# design.net
KiCad netlist of a schematic drawn in EasyEDA Pro
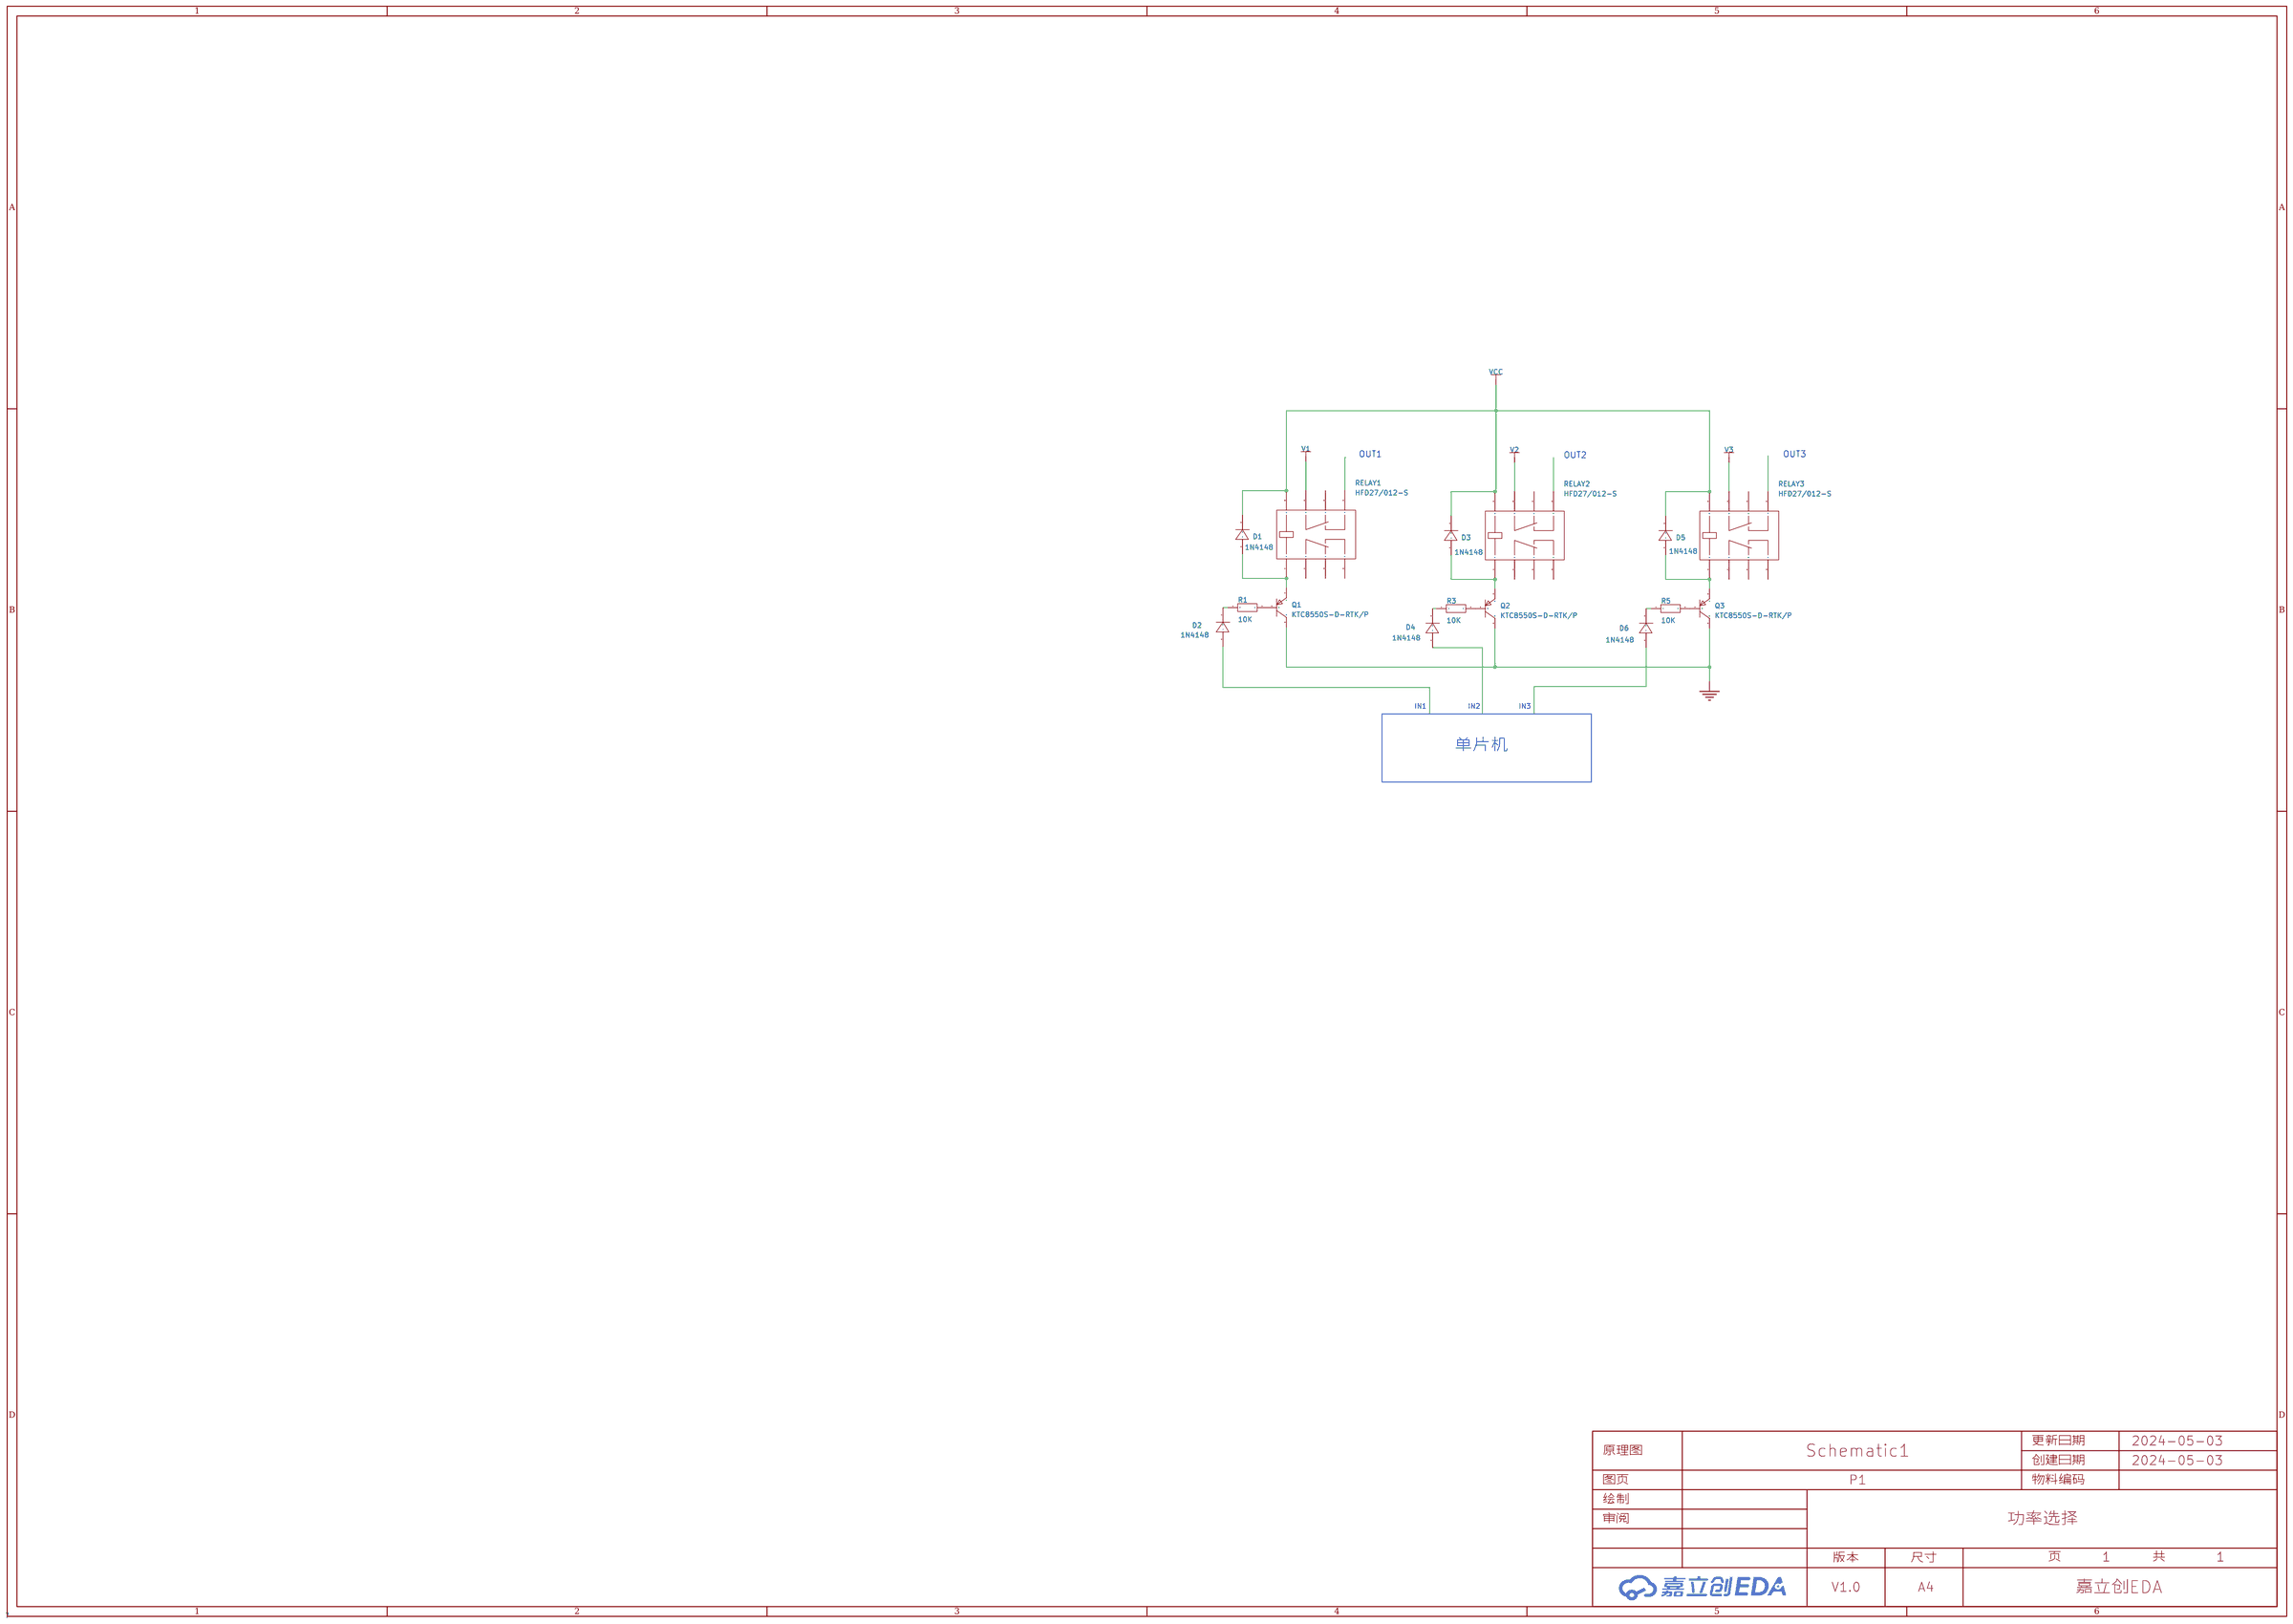
[diagram p0: schematic sheet]

(export (version "E")
  (design (tool "Eeschema 10.0.6"))
  (components
    (comp (ref "D1")
      (value "1N4148")
      (footprint "easyedapro:DO-35_BD2.0-L4.2-P8.20-D0.5-RD")
      (description "二极管配置:-;正向压降(Vf):1V@10mA;直流反向耐压(Vr):75V;平均整流电流(Io):150mA;功率:500mW;反向恢复时间(trr):4ns;")
      (fields (field (name "Manufacturer") "LGE(鲁光)"))
      (libsource (lib "easyedapro") (part "1N4148_C402212"))
    )
    (comp (ref "D2")
      (value "1N4148")
      (footprint "easyedapro:DO-35_BD2.0-L4.2-P8.20-D0.5-RD")
      (description "二极管配置:-;正向压降(Vf):1V@10mA;直流反向耐压(Vr):75V;平均整流电流(Io):150mA;功率:500mW;反向恢复时间(trr):4ns;")
      (fields (field (name "Manufacturer") "LGE(鲁光)"))
      (libsource (lib "easyedapro") (part "1N4148_C402212"))
    )
    (comp (ref "D3")
      (value "1N4148")
      (footprint "easyedapro:DO-35_BD2.0-L4.2-P8.20-D0.5-RD")
      (description "二极管配置:-;正向压降(Vf):1V@10mA;直流反向耐压(Vr):75V;平均整流电流(Io):150mA;功率:500mW;反向恢复时间(trr):4ns;")
      (fields (field (name "Manufacturer") "LGE(鲁光)"))
      (libsource (lib "easyedapro") (part "1N4148_C402212"))
    )
    (comp (ref "D4")
      (value "1N4148")
      (footprint "easyedapro:DO-35_BD2.0-L4.2-P8.20-D0.5-RD")
      (description "二极管配置:-;正向压降(Vf):1V@10mA;直流反向耐压(Vr):75V;平均整流电流(Io):150mA;功率:500mW;反向恢复时间(trr):4ns;")
      (fields (field (name "Manufacturer") "LGE(鲁光)"))
      (libsource (lib "easyedapro") (part "1N4148_C402212"))
    )
    (comp (ref "D5")
      (value "1N4148")
      (footprint "easyedapro:DO-35_BD2.0-L4.2-P8.20-D0.5-RD")
      (description "二极管配置:-;正向压降(Vf):1V@10mA;直流反向耐压(Vr):75V;平均整流电流(Io):150mA;功率:500mW;反向恢复时间(trr):4ns;")
      (fields (field (name "Manufacturer") "LGE(鲁光)"))
      (libsource (lib "easyedapro") (part "1N4148_C402212"))
    )
    (comp (ref "D6")
      (value "1N4148")
      (footprint "easyedapro:DO-35_BD2.0-L4.2-P8.20-D0.5-RD")
      (description "二极管配置:-;正向压降(Vf):1V@10mA;直流反向耐压(Vr):75V;平均整流电流(Io):150mA;功率:500mW;反向恢复时间(trr):4ns;")
      (fields (field (name "Manufacturer") "LGE(鲁光)"))
      (libsource (lib "easyedapro") (part "1N4148_C402212"))
    )
    (comp (ref "Q1")
      (value "KTC8550S-D-RTK/P")
      (footprint "easyedapro:SOT-23-3_L2.9-W1.3-P1.90-LS2.4-TR-CW")
      (description "晶体管类型:PNP;集电极电流(Ic):800mA;集射极击穿电压(Vceo):30V;功率(Pd):350mW;直流电流增益(hFE@Ic,Vce):100@50mA,1V;")
      (fields (field (name "Manufacturer") "KEC"))
      (libsource (lib "easyedapro") (part "KTC8550S-D-RTK/P"))
    )
    (comp (ref "Q2")
      (value "KTC8550S-D-RTK/P")
      (footprint "easyedapro:SOT-23-3_L2.9-W1.3-P1.90-LS2.4-TR-CW")
      (description "晶体管类型:PNP;集电极电流(Ic):800mA;集射极击穿电压(Vceo):30V;功率(Pd):350mW;直流电流增益(hFE@Ic,Vce):100@50mA,1V;")
      (fields (field (name "Manufacturer") "KEC"))
      (libsource (lib "easyedapro") (part "KTC8550S-D-RTK/P"))
    )
    (comp (ref "Q3")
      (value "KTC8550S-D-RTK/P")
      (footprint "easyedapro:SOT-23-3_L2.9-W1.3-P1.90-LS2.4-TR-CW")
      (description "晶体管类型:PNP;集电极电流(Ic):800mA;集射极击穿电压(Vceo):30V;功率(Pd):350mW;直流电流增益(hFE@Ic,Vce):100@50mA,1V;")
      (fields (field (name "Manufacturer") "KEC"))
      (libsource (lib "easyedapro") (part "KTC8550S-D-RTK/P"))
    )
    (comp (ref "R1") (value "10K") (footprint "easyedapro:R0603") (libsource (lib "easyedapro") (part "电阻")))
    (comp (ref "R3") (value "10K") (footprint "easyedapro:R0603") (libsource (lib "easyedapro") (part "电阻")))
    (comp (ref "R5") (value "10K") (footprint "easyedapro:R0603") (libsource (lib "easyedapro") (part "电阻")))
    (comp (ref "RELAY1")
      (value "HFD27/012-S")
      (footprint "easyedapro:RELAY-TH_HFD27-012-S")
      (description "线圈电压:12V;触点形式:两组转换:2C(双刀双掷-转换);触点容量(电阻负载):2A@30VDC；1A@125VAC;最大切换电压:120V@DC；240V@AC;最大切换电流:2A;")
      (fields (field (name "Manufacturer") "HF(宏发)"))
      (libsource (lib "easyedapro") (part "HFD27/012-S"))
    )
    (comp (ref "RELAY2")
      (value "HFD27/012-S")
      (footprint "easyedapro:RELAY-TH_HFD27-012-S")
      (description "线圈电压:12V;触点形式:两组转换:2C(双刀双掷-转换);触点容量(电阻负载):2A@30VDC；1A@125VAC;最大切换电压:120V@DC；240V@AC;最大切换电流:2A;")
      (fields (field (name "Manufacturer") "HF(宏发)"))
      (libsource (lib "easyedapro") (part "HFD27/012-S"))
    )
    (comp (ref "RELAY3")
      (value "HFD27/012-S")
      (footprint "easyedapro:RELAY-TH_HFD27-012-S")
      (description "线圈电压:12V;触点形式:两组转换:2C(双刀双掷-转换);触点容量(电阻负载):2A@30VDC；1A@125VAC;最大切换电压:120V@DC；240V@AC;最大切换电流:2A;")
      (fields (field (name "Manufacturer") "HF(宏发)"))
      (libsource (lib "easyedapro") (part "HFD27/012-S"))
    )
  )
  (nets
    (net (code "1") (name "GND") (class "Default")
      (node (ref "Q1") (pin "3") (pinfunction "C_3") (pintype "input"))
      (node (ref "Q2") (pin "3") (pinfunction "C_3") (pintype "input"))
      (node (ref "Q3") (pin "3") (pinfunction "C_3") (pintype "input"))
    )
    (net (code "2") (name "Net-(D1-A)") (class "Default")
      (node (ref "D1") (pin "2") (pinfunction "A_2") (pintype "unspecified"))
      (node (ref "Q1") (pin "1") (pinfunction "E_1") (pintype "input"))
      (node (ref "RELAY1") (pin "1") (pinfunction "1_1") (pintype "input"))
    )
    (net (code "3") (name "Net-(D2-C)") (class "Default")
      (node (ref "D2") (pin "1") (pinfunction "C_1") (pintype "unspecified"))
      (node (ref "R1") (pin "1") (pinfunction "1_1") (pintype "input"))
    )
    (net (code "4") (name "Net-(D3-A)") (class "Default")
      (node (ref "D3") (pin "2") (pinfunction "A_2") (pintype "unspecified"))
      (node (ref "Q2") (pin "1") (pinfunction "E_1") (pintype "input"))
      (node (ref "RELAY2") (pin "1") (pinfunction "1_1") (pintype "input"))
    )
    (net (code "5") (name "Net-(D4-C)") (class "Default")
      (node (ref "D4") (pin "1") (pinfunction "C_1") (pintype "unspecified"))
      (node (ref "R3") (pin "1") (pinfunction "1_1") (pintype "input"))
    )
    (net (code "6") (name "Net-(D5-A)") (class "Default")
      (node (ref "D5") (pin "2") (pinfunction "A_2") (pintype "unspecified"))
      (node (ref "Q3") (pin "1") (pinfunction "E_1") (pintype "input"))
      (node (ref "RELAY3") (pin "1") (pinfunction "1_1") (pintype "input"))
    )
    (net (code "7") (name "Net-(D6-C)") (class "Default")
      (node (ref "D6") (pin "1") (pinfunction "C_1") (pintype "unspecified"))
      (node (ref "R5") (pin "1") (pinfunction "1_1") (pintype "input"))
    )
    (net (code "8") (name "Net-(Q1-B)") (class "Default")
      (node (ref "Q1") (pin "2") (pinfunction "B_2") (pintype "input"))
      (node (ref "R1") (pin "2") (pinfunction "2_2") (pintype "input"))
    )
    (net (code "9") (name "Net-(Q2-B)") (class "Default")
      (node (ref "Q2") (pin "2") (pinfunction "B_2") (pintype "input"))
      (node (ref "R3") (pin "2") (pinfunction "2_2") (pintype "input"))
    )
    (net (code "10") (name "Net-(Q3-B)") (class "Default")
      (node (ref "Q3") (pin "2") (pinfunction "B_2") (pintype "input"))
      (node (ref "R5") (pin "2") (pinfunction "2_2") (pintype "input"))
    )
    (net (code "11") (name "V1") (class "Default")
      (node (ref "RELAY1") (pin "13") (pinfunction "13_13") (pintype "input"))
    )
    (net (code "12") (name "V2") (class "Default")
      (node (ref "RELAY2") (pin "13") (pinfunction "13_13") (pintype "input"))
    )
    (net (code "13") (name "V3") (class "Default")
      (node (ref "RELAY3") (pin "13") (pinfunction "13_13") (pintype "input"))
    )
    (net (code "14") (name "VCC") (class "Default")
      (node (ref "D1") (pin "1") (pinfunction "C_1") (pintype "unspecified"))
      (node (ref "D3") (pin "1") (pinfunction "C_1") (pintype "unspecified"))
      (node (ref "D5") (pin "1") (pinfunction "C_1") (pintype "unspecified"))
      (node (ref "RELAY1") (pin "16") (pinfunction "16_16") (pintype "input"))
      (node (ref "RELAY2") (pin "16") (pinfunction "16_16") (pintype "input"))
      (node (ref "RELAY3") (pin "16") (pinfunction "16_16") (pintype "input"))
    )
    (net (code "15") (name "unconnected-(D2-A-Pad2)") (class "Default")
      (node (ref "D2") (pin "2") (pinfunction "A_2") (pintype "unspecified"))
    )
    (net (code "16") (name "unconnected-(D4-A-Pad2)") (class "Default")
      (node (ref "D4") (pin "2") (pinfunction "A_2") (pintype "unspecified"))
    )
    (net (code "17") (name "unconnected-(D6-A-Pad2)") (class "Default")
      (node (ref "D6") (pin "2") (pinfunction "A_2") (pintype "unspecified"))
    )
    (net (code "18") (name "unconnected-(RELAY1-Pad4)") (class "Default")
      (node (ref "RELAY1") (pin "4") (pinfunction "4_4") (pintype "input"))
    )
    (net (code "19") (name "unconnected-(RELAY1-Pad6)") (class "Default")
      (node (ref "RELAY1") (pin "6") (pinfunction "6_6") (pintype "input"))
    )
    (net (code "20") (name "unconnected-(RELAY1-Pad8)") (class "Default")
      (node (ref "RELAY1") (pin "8") (pinfunction "8_8") (pintype "input"))
    )
    (net (code "21") (name "unconnected-(RELAY1-Pad9)") (class "Default")
      (node (ref "RELAY1") (pin "9") (pinfunction "9_9") (pintype "input"))
    )
    (net (code "22") (name "unconnected-(RELAY1-Pad11)") (class "Default")
      (node (ref "RELAY1") (pin "11") (pinfunction "11_11") (pintype "input"))
    )
    (net (code "23") (name "unconnected-(RELAY2-Pad4)") (class "Default")
      (node (ref "RELAY2") (pin "4") (pinfunction "4_4") (pintype "input"))
    )
    (net (code "24") (name "unconnected-(RELAY2-Pad6)") (class "Default")
      (node (ref "RELAY2") (pin "6") (pinfunction "6_6") (pintype "input"))
    )
    (net (code "25") (name "unconnected-(RELAY2-Pad8)") (class "Default")
      (node (ref "RELAY2") (pin "8") (pinfunction "8_8") (pintype "input"))
    )
    (net (code "26") (name "unconnected-(RELAY2-Pad9)") (class "Default")
      (node (ref "RELAY2") (pin "9") (pinfunction "9_9") (pintype "input"))
    )
    (net (code "27") (name "unconnected-(RELAY2-Pad11)") (class "Default")
      (node (ref "RELAY2") (pin "11") (pinfunction "11_11") (pintype "input"))
    )
    (net (code "28") (name "unconnected-(RELAY3-Pad4)") (class "Default")
      (node (ref "RELAY3") (pin "4") (pinfunction "4_4") (pintype "input"))
    )
    (net (code "29") (name "unconnected-(RELAY3-Pad6)") (class "Default")
      (node (ref "RELAY3") (pin "6") (pinfunction "6_6") (pintype "input"))
    )
    (net (code "30") (name "unconnected-(RELAY3-Pad8)") (class "Default")
      (node (ref "RELAY3") (pin "8") (pinfunction "8_8") (pintype "input"))
    )
    (net (code "31") (name "unconnected-(RELAY3-Pad9)") (class "Default")
      (node (ref "RELAY3") (pin "9") (pinfunction "9_9") (pintype "input"))
    )
    (net (code "32") (name "unconnected-(RELAY3-Pad11)") (class "Default")
      (node (ref "RELAY3") (pin "11") (pinfunction "11_11") (pintype "input"))
    )
  )
)
